# Connectors.net
KiCad netlist of a schematic drawn in Altium Designer
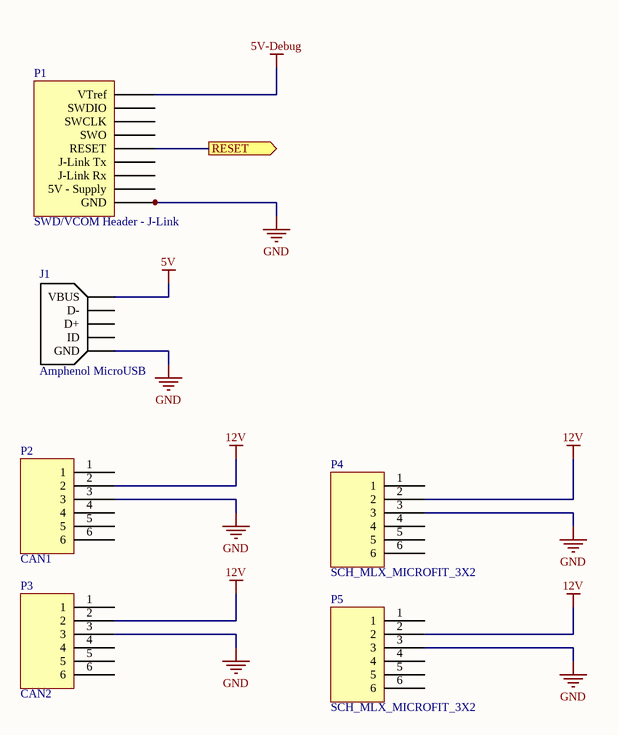
[diagram p0: Connectors.SchDoc]

(export (version "E")
  (design (tool "Eeschema 10.0.6"))
  (components
    (comp (ref "J1")
      (value "Amphenol MicroUSB")
      (footprint "Amphenol MicroUSB")
      (libsource (lib "Amphenol MicroUSB") (part "Amphenol MicroUSB - 609-4618-1-ND"))
    )
    (comp (ref "P1")
      (value "SWD/VCOM Header - J-Link")
      (footprint "20 Pin 100 Mil Shrouded header with key")
      (libsource (lib "Samtec SWD+VCOM Header - J-Link") (part "SWD/VCOM Header"))
    )
    (comp (ref "P2")
      (value "CAN1")
      (footprint "PCB_MLX_MICROFIT_3X2:PCB_MLX_MICROFIT_3X2")
      (libsource (lib "Molex Microfit 2.0 3x2") (part "SCH_MLX_MICROFIT_3X2"))
    )
    (comp (ref "P3")
      (value "CAN2")
      (footprint "PCB_MLX_MICROFIT_3X2:PCB_MLX_MICROFIT_3X2")
      (libsource (lib "Molex Microfit 2.0 3x2") (part "SCH_MLX_MICROFIT_3X2"))
    )
    (comp (ref "P4")
      (value "SCH_MLX_MICROFIT_3X2")
      (footprint "PCB_MLX_MICROFIT_3X2:PCB_MLX_MICROFIT_3X2")
      (libsource (lib "Molex Microfit 2.0 3x2") (part "SCH_MLX_MICROFIT_3X2"))
    )
    (comp (ref "P5")
      (value "SCH_MLX_MICROFIT_3X2")
      (footprint "PCB_MLX_MICROFIT_3X2:PCB_MLX_MICROFIT_3X2")
      (libsource (lib "Molex Microfit 2.0 3x2") (part "SCH_MLX_MICROFIT_3X2"))
    )
  )
  (nets
    (net (code "1") (name "/RESET") (class "Default")
      (node (ref "P1") (pin "15") (pinfunction "RESET_15") (pintype "passive"))
    )
    (net (code "2") (name "5V") (class "Default")
      (node (ref "J1") (pin "1") (pinfunction "VBUS_1") (pintype "passive"))
    )
    (net (code "3") (name "5V-Debug") (class "Default")
      (node (ref "P1") (pin "1") (pinfunction "VTref_1") (pintype "passive"))
    )
    (net (code "4") (name "12V") (class "Default")
      (node (ref "P2") (pin "2") (pinfunction "2_2") (pintype "passive"))
      (node (ref "P3") (pin "2") (pinfunction "2_2") (pintype "passive"))
      (node (ref "P4") (pin "2") (pinfunction "2_2") (pintype "passive"))
      (node (ref "P5") (pin "2") (pinfunction "2_2") (pintype "passive"))
    )
    (net (code "5") (name "GND") (class "Default")
      (node (ref "J1") (pin "5") (pinfunction "GND_5") (pintype "passive"))
      (node (ref "P1") (pin "10") (pinfunction "GND_10") (pintype "passive"))
      (node (ref "P1") (pin "12") (pinfunction "GND_12") (pintype "passive"))
      (node (ref "P1") (pin "4") (pinfunction "GND_4") (pintype "passive"))
      (node (ref "P1") (pin "6") (pinfunction "GND_6") (pintype "passive"))
      (node (ref "P1") (pin "8") (pinfunction "GND_8") (pintype "passive"))
      (node (ref "P2") (pin "3") (pinfunction "3_3") (pintype "passive"))
      (node (ref "P3") (pin "3") (pinfunction "3_3") (pintype "passive"))
      (node (ref "P4") (pin "3") (pinfunction "3_3") (pintype "passive"))
      (node (ref "P5") (pin "3") (pinfunction "3_3") (pintype "passive"))
    )
    (net (code "6") (name "unconnected-(J1-D+-Pad3)") (class "Default")
      (node (ref "J1") (pin "3") (pinfunction "D+_3") (pintype "passive"))
    )
    (net (code "7") (name "unconnected-(J1-D--Pad2)") (class "Default")
      (node (ref "J1") (pin "2") (pinfunction "D-_2") (pintype "passive"))
    )
    (net (code "8") (name "unconnected-(J1-ID-Pad4)") (class "Default")
      (node (ref "J1") (pin "4") (pinfunction "ID_4") (pintype "passive"))
    )
    (net (code "9") (name "unconnected-(P1-5V_-_Supply-Pad19)") (class "Default")
      (node (ref "P1") (pin "19") (pinfunction "5V_-_Supply_19") (pintype "passive"))
    )
    (net (code "10") (name "unconnected-(P1-J-Link_Rx-Pad17)") (class "Default")
      (node (ref "P1") (pin "17") (pinfunction "J-Link_Rx_17") (pintype "passive"))
    )
    (net (code "11") (name "unconnected-(P1-J-Link_Tx-Pad5)") (class "Default")
      (node (ref "P1") (pin "5") (pinfunction "J-Link_Tx_5") (pintype "passive"))
    )
    (net (code "12") (name "unconnected-(P1-SWCLK-Pad9)") (class "Default")
      (node (ref "P1") (pin "9") (pinfunction "SWCLK_9") (pintype "passive"))
    )
    (net (code "13") (name "unconnected-(P1-SWDIO-Pad7)") (class "Default")
      (node (ref "P1") (pin "7") (pinfunction "SWDIO_7") (pintype "passive"))
    )
    (net (code "14") (name "unconnected-(P1-SWO-Pad13)") (class "Default")
      (node (ref "P1") (pin "13") (pinfunction "SWO_13") (pintype "passive"))
    )
    (net (code "15") (name "unconnected-(P2-Pad1)") (class "Default")
      (node (ref "P2") (pin "1") (pinfunction "1_1") (pintype "passive"))
    )
    (net (code "16") (name "unconnected-(P2-Pad4)") (class "Default")
      (node (ref "P2") (pin "4") (pinfunction "4_4") (pintype "passive"))
    )
    (net (code "17") (name "unconnected-(P2-Pad5)") (class "Default")
      (node (ref "P2") (pin "5") (pinfunction "5_5") (pintype "passive"))
    )
    (net (code "18") (name "unconnected-(P2-Pad6)") (class "Default")
      (node (ref "P2") (pin "6") (pinfunction "6_6") (pintype "passive"))
    )
    (net (code "19") (name "unconnected-(P3-Pad1)") (class "Default")
      (node (ref "P3") (pin "1") (pinfunction "1_1") (pintype "passive"))
    )
    (net (code "20") (name "unconnected-(P3-Pad4)") (class "Default")
      (node (ref "P3") (pin "4") (pinfunction "4_4") (pintype "passive"))
    )
    (net (code "21") (name "unconnected-(P3-Pad5)") (class "Default")
      (node (ref "P3") (pin "5") (pinfunction "5_5") (pintype "passive"))
    )
    (net (code "22") (name "unconnected-(P3-Pad6)") (class "Default")
      (node (ref "P3") (pin "6") (pinfunction "6_6") (pintype "passive"))
    )
    (net (code "23") (name "unconnected-(P4-Pad1)") (class "Default")
      (node (ref "P4") (pin "1") (pinfunction "1_1") (pintype "passive"))
    )
    (net (code "24") (name "unconnected-(P4-Pad4)") (class "Default")
      (node (ref "P4") (pin "4") (pinfunction "4_4") (pintype "passive"))
    )
    (net (code "25") (name "unconnected-(P4-Pad5)") (class "Default")
      (node (ref "P4") (pin "5") (pinfunction "5_5") (pintype "passive"))
    )
    (net (code "26") (name "unconnected-(P4-Pad6)") (class "Default")
      (node (ref "P4") (pin "6") (pinfunction "6_6") (pintype "passive"))
    )
    (net (code "27") (name "unconnected-(P5-Pad1)") (class "Default")
      (node (ref "P5") (pin "1") (pinfunction "1_1") (pintype "passive"))
    )
    (net (code "28") (name "unconnected-(P5-Pad4)") (class "Default")
      (node (ref "P5") (pin "4") (pinfunction "4_4") (pintype "passive"))
    )
    (net (code "29") (name "unconnected-(P5-Pad5)") (class "Default")
      (node (ref "P5") (pin "5") (pinfunction "5_5") (pintype "passive"))
    )
    (net (code "30") (name "unconnected-(P5-Pad6)") (class "Default")
      (node (ref "P5") (pin "6") (pinfunction "6_6") (pintype "passive"))
    )
  )
)
